# CABLE_2.net
KiCad netlist of a schematic drawn in EAGLE
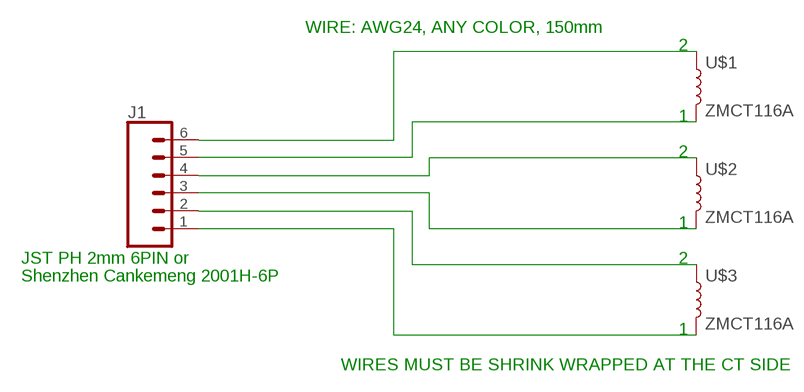
[diagram p0: schematic, sheet 1]

(export (version "E")
  (design (tool "Eeschema 10.0.6"))
  (components
    (comp (ref "J1")
      (value "CONN_06LONGPADS")
      (footprint "eagle-import:1X06_LONGPADS")
      (libsource (lib "eagle-import") (part "CONN_06LONGPADS"))
    )
    (comp (ref "U$1")
      (value "ZMCT116A")
      (footprint "eagle-import:ZMCT116A")
      (libsource (lib "eagle-import") (part "ZMCT116A"))
    )
    (comp (ref "U$2")
      (value "ZMCT116A")
      (footprint "eagle-import:ZMCT116A")
      (libsource (lib "eagle-import") (part "ZMCT116A"))
    )
    (comp (ref "U$3")
      (value "ZMCT116A")
      (footprint "eagle-import:ZMCT116A")
      (libsource (lib "eagle-import") (part "ZMCT116A"))
    )
  )
  (nets
    (net (code "1") (name "Net-(U$1-1)") (class "Default")
      (node (ref "J1") (pin "6") (pinfunction "6_6") (pintype "passive"))
      (node (ref "U$1") (pin "P$1") (pinfunction "1_P$1") (pintype "passive"))
    )
    (net (code "2") (name "Net-(U$1-2)") (class "Default")
      (node (ref "J1") (pin "5") (pinfunction "5_5") (pintype "passive"))
      (node (ref "U$1") (pin "P$2") (pinfunction "2_P$2") (pintype "passive"))
    )
    (net (code "3") (name "Net-(U$2-1)") (class "Default")
      (node (ref "J1") (pin "4") (pinfunction "4_4") (pintype "passive"))
      (node (ref "U$2") (pin "P$1") (pinfunction "1_P$1") (pintype "passive"))
    )
    (net (code "4") (name "Net-(U$2-2)") (class "Default")
      (node (ref "J1") (pin "3") (pinfunction "3_3") (pintype "passive"))
      (node (ref "U$2") (pin "P$2") (pinfunction "2_P$2") (pintype "passive"))
    )
    (net (code "5") (name "Net-(U$3-1)") (class "Default")
      (node (ref "J1") (pin "2") (pinfunction "2_2") (pintype "passive"))
      (node (ref "U$3") (pin "P$1") (pinfunction "1_P$1") (pintype "passive"))
    )
    (net (code "6") (name "Net-(U$3-2)") (class "Default")
      (node (ref "J1") (pin "1") (pinfunction "1_1") (pintype "passive"))
      (node (ref "U$3") (pin "P$2") (pinfunction "2_P$2") (pintype "passive"))
    )
  )
)
